# BG95_Power.net
KiCad netlist of a schematic drawn in Altium Designer
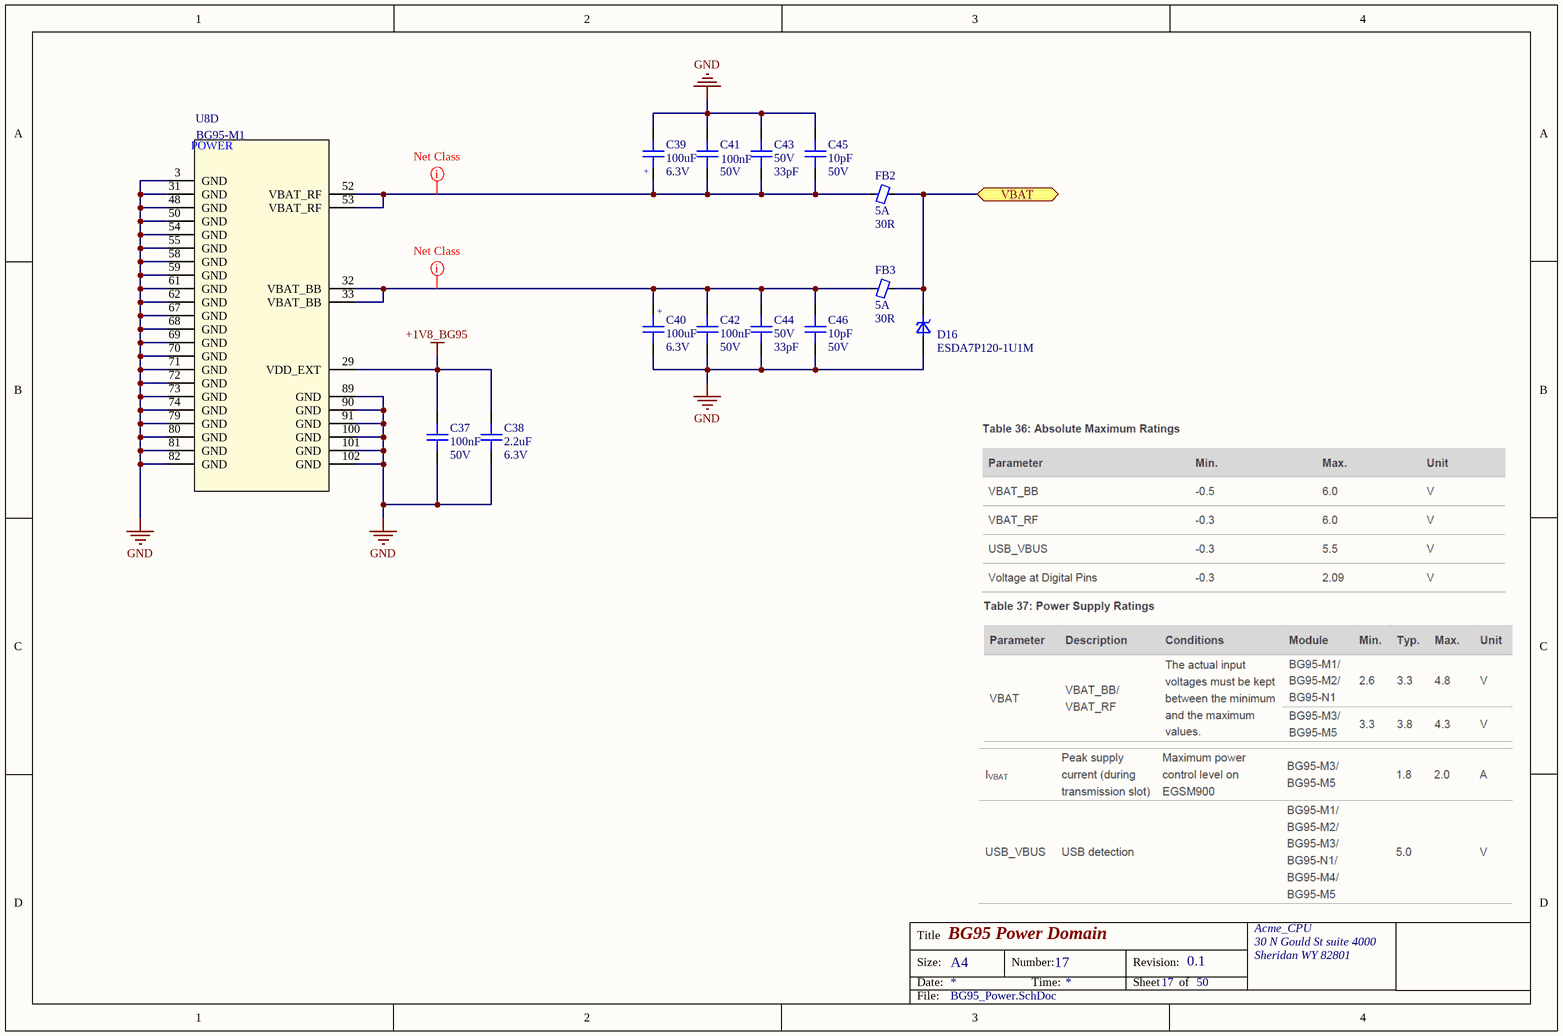
[diagram p0: BG95_Power.SchDoc]

(export (version "E")
  (design (tool "Eeschema 10.0.6"))
  (components
    (comp (ref "C37")
      (value "CAP CER 0.1UF 50V X7R 0402")
      (footprint "C0402")
      (description "0.1µF ±10% 50V Ceramic Capacitor X7R 0402 (1005 Metric)")
      (fields
        (field (name "MANUFACTURER") "TDK")
        (field (name "MANUFACTURER PART NUMBER") "CGA2B3X7R1H104K050BB")
        (field (name "CAPACITANCE") "100nF")
        (field (name "VOLTAGE") "50V")
      )
      (libsource (lib "capacitors_smd") (part "CAP CER 0.1UF 50V X7R 0402"))
    )
    (comp (ref "C38")
      (value "CAP CER 2.2UF 6.3V X5R 0402")
      (footprint "C0402")
      (description "2.2µF ±20% 6.3V Ceramic Capacitor X5R 0402 (1005 Metric)")
      (fields
        (field (name "MANUFACTURER") "Murata")
        (field (name "MANUFACTURER PART NUMBER") "GRM155R60J225ME15D")
        (field (name "CAPACITANCE") "2.2uF")
        (field (name "VOLTAGE") "6.3V")
      )
      (libsource (lib "capacitors_smd") (part "CAP CER 2.2UF 6.3V X5R 0402"))
    )
    (comp (ref "C39")
      (value "CAP ALUM 100 UF 20% 6.3 V SMD")
      (footprint "WCAP-ASLI_5x5.5")
      (description "100µF 6.3V Aluminum Electrolytic Capacitors Radial, Can - SMD  2000 Hrs @ 105°C")
      (fields
        (field (name "MANUFACTURER") "Wurth Elektronik")
        (field (name "MANUFACTURER PART NUMBER") "865080142007")
        (field (name "CAPACITANCE") "100uF")
        (field (name "VOLTAGE RATING") "6.3V")
      )
      (libsource (lib "capacitors_alum_electr_poly") (part "CAP ALUM 100 UF 20% 6.3 V SMD"))
    )
    (comp (ref "C40")
      (value "CAP ALUM 100 UF 20% 6.3 V SMD")
      (footprint "WCAP-ASLI_5x5.5")
      (description "100µF 6.3V Aluminum Electrolytic Capacitors Radial, Can - SMD  2000 Hrs @ 105°C")
      (fields
        (field (name "MANUFACTURER") "Wurth Elektronik")
        (field (name "MANUFACTURER PART NUMBER") "865080142007")
        (field (name "CAPACITANCE") "100uF")
        (field (name "VOLTAGE RATING") "6.3V")
      )
      (libsource (lib "capacitors_alum_electr_poly") (part "CAP ALUM 100 UF 20% 6.3 V SMD"))
    )
    (comp (ref "C41")
      (value "CAP CER 0.1UF 50V X7R 0402")
      (footprint "C0402")
      (description "0.1µF ±10% 50V Ceramic Capacitor X7R 0402 (1005 Metric)")
      (fields
        (field (name "MANUFACTURER") "TDK")
        (field (name "MANUFACTURER PART NUMBER") "CGA2B3X7R1H104K050BB")
        (field (name "CAPACITANCE") "100nF")
        (field (name "VOLTAGE") "50V")
      )
      (libsource (lib "capacitors_smd") (part "CAP CER 0.1UF 50V X7R 0402"))
    )
    (comp (ref "C42")
      (value "CAP CER 0.1UF 50V X7R 0402")
      (footprint "C0402")
      (description "0.1µF ±10% 50V Ceramic Capacitor X7R 0402 (1005 Metric)")
      (fields
        (field (name "MANUFACTURER") "TDK")
        (field (name "MANUFACTURER PART NUMBER") "CGA2B3X7R1H104K050BB")
        (field (name "CAPACITANCE") "100nF")
        (field (name "VOLTAGE") "50V")
      )
      (libsource (lib "capacitors_smd") (part "CAP CER 0.1UF 50V X7R 0402"))
    )
    (comp (ref "C43")
      (value "CAP CER 33PF 50V C0G/NPO 0402")
      (footprint "C0402")
      (description "33pF ±5% 50V Ceramic Capacitor C0G, NP0 0402 (1005 Metric)")
      (fields
        (field (name "MANUFACTURER") "Yageo")
        (field (name "MANUFACTURER PART NUMBER") "CC0402JRNPO9BN330")
        (field (name "VOLTAGE RATING") "50V")
        (field (name "CAPACITANCE") "33pF")
      )
      (libsource (lib "capacitors_smd") (part "CAP CER 33PF 50V C0G/NPO 0402"))
    )
    (comp (ref "C44")
      (value "CAP CER 33PF 50V C0G/NPO 0402")
      (footprint "C0402")
      (description "33pF ±5% 50V Ceramic Capacitor C0G, NP0 0402 (1005 Metric)")
      (fields
        (field (name "MANUFACTURER") "Yageo")
        (field (name "MANUFACTURER PART NUMBER") "CC0402JRNPO9BN330")
        (field (name "VOLTAGE RATING") "50V")
        (field (name "CAPACITANCE") "33pF")
      )
      (libsource (lib "capacitors_smd") (part "CAP CER 33PF 50V C0G/NPO 0402"))
    )
    (comp (ref "C45")
      (value "CAP CER 10PF 50V C0G/NP0 0402")
      (footprint "C0402")
      (description "10pF ±10% 50V Ceramic Capacitor C0G, NP0 0402 (1005 Metric)")
      (fields
        (field (name "MANUFACTURER") "KEMET")
        (field (name "MANUFACTURER PART NUMBER") "C0402C100K5GACTU")
        (field (name "CAPACITANCE") "10pF")
        (field (name "VOLTAGE RATING") "50V")
      )
      (libsource (lib "capacitors_smd") (part "CAP CER 10PF 50V C0G/NP0 0402"))
    )
    (comp (ref "C46")
      (value "CAP CER 10PF 50V C0G/NP0 0402")
      (footprint "C0402")
      (description "10pF ±10% 50V Ceramic Capacitor C0G, NP0 0402 (1005 Metric)")
      (fields
        (field (name "MANUFACTURER") "KEMET")
        (field (name "MANUFACTURER PART NUMBER") "C0402C100K5GACTU")
        (field (name "CAPACITANCE") "10pF")
        (field (name "VOLTAGE RATING") "50V")
      )
      (libsource (lib "capacitors_smd") (part "CAP CER 10PF 50V C0G/NP0 0402"))
    )
    (comp (ref "D16")
      (value "ESDA7P120-1U1M")
      (footprint "ST_QFN_1610")
      (description "11.5V Clamp 120A (8/20µs) Ipp Tvs Diode Surface Mount 1610")
      (fields (field (name "MANUFACTURER") "STMicroelectronics"))
      (libsource (lib "diodes_tvs") (part "TVS DIODE ESDA7P120-1U1M 5.5V 11.5V 1610"))
    )
    (comp (ref "FB2")
      (value "MPZ1608S300ATAH0")
      (footprint "L0603")
      (description "30 Ohms @ 100MHz 1 Power Line Ferrite Bead 0603 (1608 Metric) 5A 10mOhm")
      (fields
        (field (name "MANUFACTURER") "TDK")
        (field (name "TOLERANCE") "25%")
        (field (name "CURRENT RATING") "5A")
        (field (name "IMPEDANCE") "30R")
      )
      (libsource (lib "ferrite_beads") (part "FERRITE BEAD 30 OHM 0603 1LN"))
    )
    (comp (ref "FB3")
      (value "MPZ1608S300ATAH0")
      (footprint "L0603")
      (description "30 Ohms @ 100MHz 1 Power Line Ferrite Bead 0603 (1608 Metric) 5A 10mOhm")
      (fields
        (field (name "MANUFACTURER") "TDK")
        (field (name "TOLERANCE") "25%")
        (field (name "CURRENT RATING") "5A")
        (field (name "IMPEDANCE") "30R")
      )
      (libsource (lib "ferrite_beads") (part "FERRITE BEAD 30 OHM 0603 1LN"))
    )
    (comp (ref "U8")
      (value "BG95-M1")
      (footprint "BG95")
      (description "LTE Cat M1, LTE Cat NB2 and EGPRS Transceiver Module Antenna Not Included Surface Mount")
      (fields (field (name "MANUFACTURER") "QUECTEL"))
      (libsource (lib "BLDC_Motor_Driver") (part "MOD BG95 RX TXRX CELLULAR LTE/NAV SMD"))
    )
  )
  (nets
    (net (code "1") (name "+1V8_BG95") (class "Default")
      (node (ref "C37") (pin "2") (pinfunction "2_2") (pintype "passive"))
      (node (ref "C38") (pin "2") (pinfunction "2_2") (pintype "passive"))
      (node (ref "U8") (pin "29") (pinfunction "VDD_EXT_29") (pintype "power_in"))
    )
    (net (code "2") (name "/VBAT") (class "Default")
      (node (ref "D16") (pin "1") (pinfunction "K_1") (pintype "passive"))
      (node (ref "FB2") (pin "2") (pinfunction "2_2") (pintype "passive"))
      (node (ref "FB3") (pin "2") (pinfunction "2_2") (pintype "passive"))
    )
    (net (code "3") (name "GND") (class "Default")
      (node (ref "C37") (pin "1") (pinfunction "1_1") (pintype "passive"))
      (node (ref "C38") (pin "1") (pinfunction "1_1") (pintype "passive"))
      (node (ref "C39") (pin "2") (pinfunction "2_2") (pintype "passive"))
      (node (ref "C40") (pin "2") (pinfunction "2_2") (pintype "passive"))
      (node (ref "C41") (pin "2") (pinfunction "2_2") (pintype "passive"))
      (node (ref "C42") (pin "1") (pinfunction "1_1") (pintype "passive"))
      (node (ref "C43") (pin "2") (pinfunction "2_2") (pintype "passive"))
      (node (ref "C44") (pin "1") (pinfunction "1_1") (pintype "passive"))
      (node (ref "C45") (pin "2") (pinfunction "2_2") (pintype "passive"))
      (node (ref "C46") (pin "1") (pinfunction "1_1") (pintype "passive"))
      (node (ref "D16") (pin "2") (pinfunction "A_2") (pintype "passive"))
      (node (ref "U8") (pin "100") (pinfunction "GND_100") (pintype "power_in"))
      (node (ref "U8") (pin "101") (pinfunction "GND_101") (pintype "power_in"))
      (node (ref "U8") (pin "102") (pinfunction "GND_102") (pintype "power_in"))
      (node (ref "U8") (pin "3") (pinfunction "GND_3") (pintype "power_in"))
      (node (ref "U8") (pin "31") (pinfunction "GND_31") (pintype "power_in"))
      (node (ref "U8") (pin "48") (pinfunction "GND_48") (pintype "power_in"))
      (node (ref "U8") (pin "50") (pinfunction "GND_50") (pintype "power_in"))
      (node (ref "U8") (pin "54") (pinfunction "GND_54") (pintype "power_in"))
      (node (ref "U8") (pin "55") (pinfunction "GND_55") (pintype "power_in"))
      (node (ref "U8") (pin "58") (pinfunction "GND_58") (pintype "power_in"))
      (node (ref "U8") (pin "59") (pinfunction "GND_59") (pintype "power_in"))
      (node (ref "U8") (pin "61") (pinfunction "GND_61") (pintype "power_in"))
      (node (ref "U8") (pin "62") (pinfunction "GND_62") (pintype "power_in"))
      (node (ref "U8") (pin "67") (pinfunction "GND_67") (pintype "power_in"))
      (node (ref "U8") (pin "68") (pinfunction "GND_68") (pintype "power_in"))
      (node (ref "U8") (pin "69") (pinfunction "GND_69") (pintype "power_in"))
      (node (ref "U8") (pin "70") (pinfunction "GND_70") (pintype "power_in"))
      (node (ref "U8") (pin "71") (pinfunction "GND_71") (pintype "power_in"))
      (node (ref "U8") (pin "72") (pinfunction "GND_72") (pintype "power_in"))
      (node (ref "U8") (pin "73") (pinfunction "GND_73") (pintype "power_in"))
      (node (ref "U8") (pin "74") (pinfunction "GND_74") (pintype "power_in"))
      (node (ref "U8") (pin "79") (pinfunction "GND_79") (pintype "power_in"))
      (node (ref "U8") (pin "80") (pinfunction "GND_80") (pintype "power_in"))
      (node (ref "U8") (pin "81") (pinfunction "GND_81") (pintype "power_in"))
      (node (ref "U8") (pin "82") (pinfunction "GND_82") (pintype "power_in"))
      (node (ref "U8") (pin "89") (pinfunction "GND_89") (pintype "power_in"))
      (node (ref "U8") (pin "90") (pinfunction "GND_90") (pintype "power_in"))
      (node (ref "U8") (pin "91") (pinfunction "GND_91") (pintype "power_in"))
    )
    (net (code "4") (name "Net-(C39-Pad1)") (class "Default")
      (node (ref "C39") (pin "1") (pinfunction "1_1") (pintype "passive"))
      (node (ref "C41") (pin "1") (pinfunction "1_1") (pintype "passive"))
      (node (ref "C43") (pin "1") (pinfunction "1_1") (pintype "passive"))
      (node (ref "C45") (pin "1") (pinfunction "1_1") (pintype "passive"))
      (node (ref "FB2") (pin "1") (pinfunction "1_1") (pintype "passive"))
      (node (ref "U8") (pin "52") (pinfunction "VBAT_RF_52") (pintype "power_in"))
      (node (ref "U8") (pin "53") (pinfunction "VBAT_RF_53") (pintype "power_in"))
    )
    (net (code "5") (name "Net-(C40-Pad1)") (class "Default")
      (node (ref "C40") (pin "1") (pinfunction "1_1") (pintype "passive"))
      (node (ref "C42") (pin "2") (pinfunction "2_2") (pintype "passive"))
      (node (ref "C44") (pin "2") (pinfunction "2_2") (pintype "passive"))
      (node (ref "C46") (pin "2") (pinfunction "2_2") (pintype "passive"))
      (node (ref "FB3") (pin "1") (pinfunction "1_1") (pintype "passive"))
      (node (ref "U8") (pin "32") (pinfunction "VBAT_BB_32") (pintype "power_in"))
      (node (ref "U8") (pin "33") (pinfunction "VBAT_BB_33") (pintype "power_in"))
    )
  )
)
